# PointController.net
KiCad netlist of a schematic drawn in EAGLE
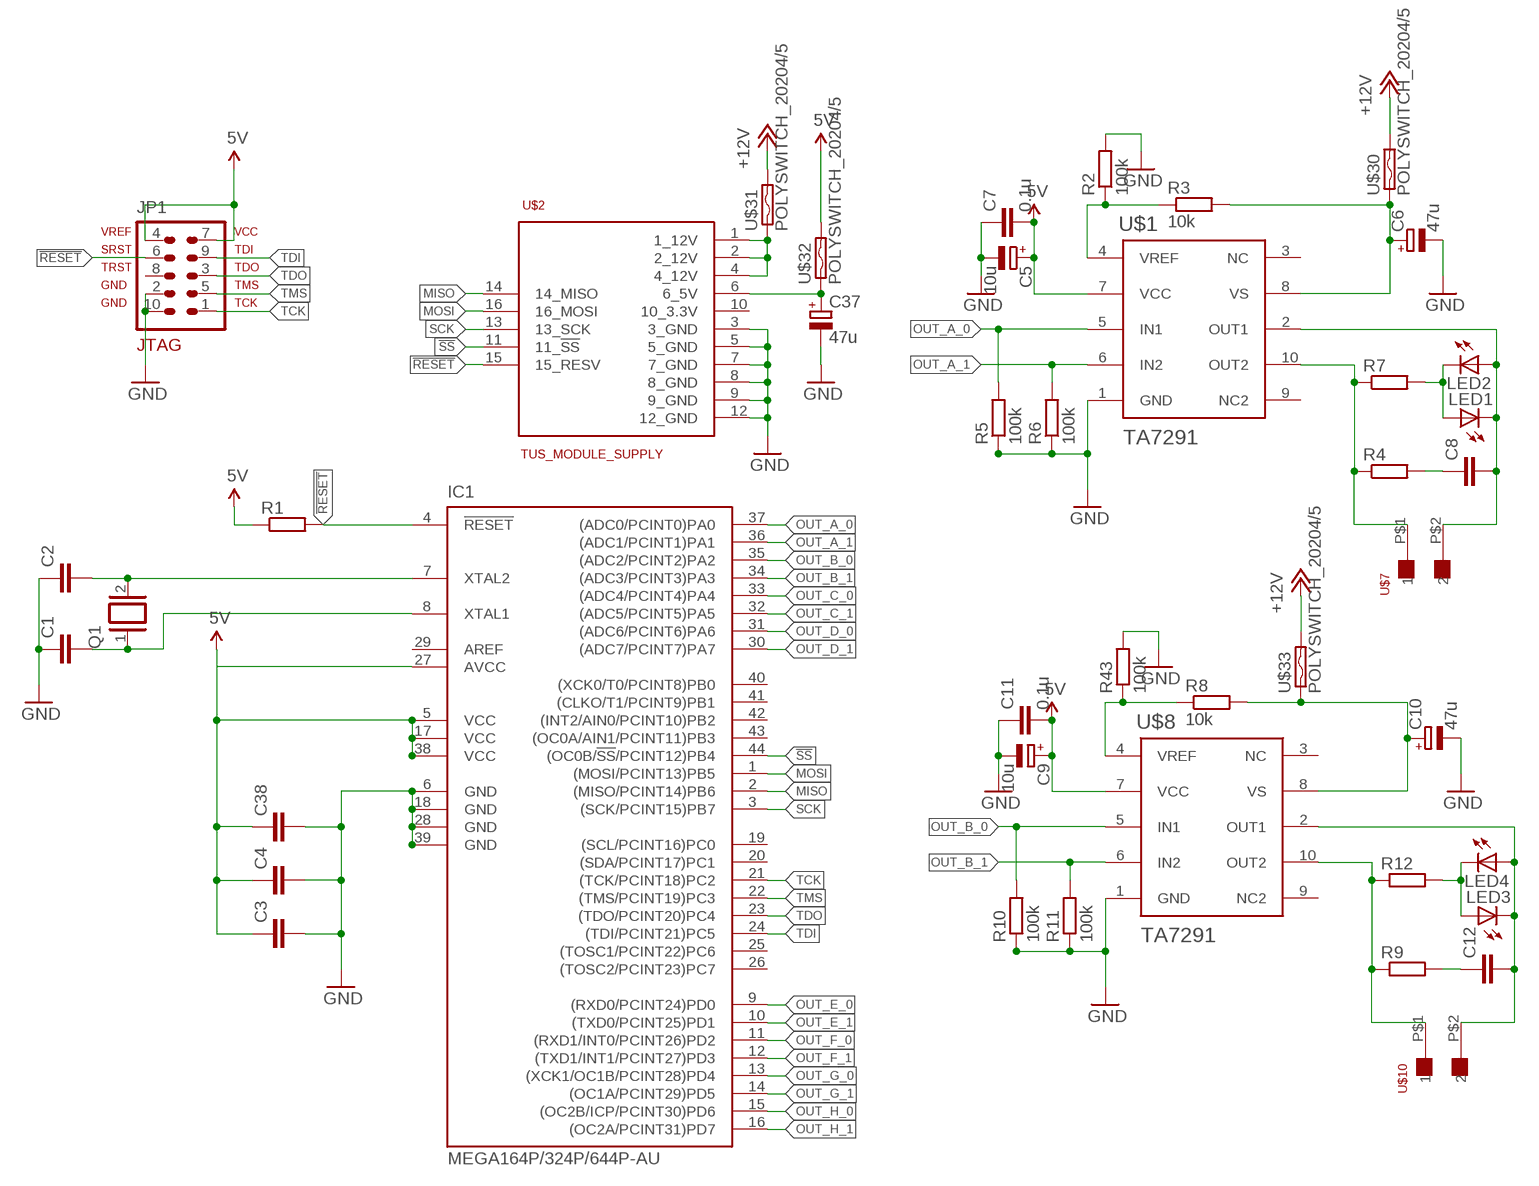
[diagram p0: schematic, sheet 1, part 1 of 2]
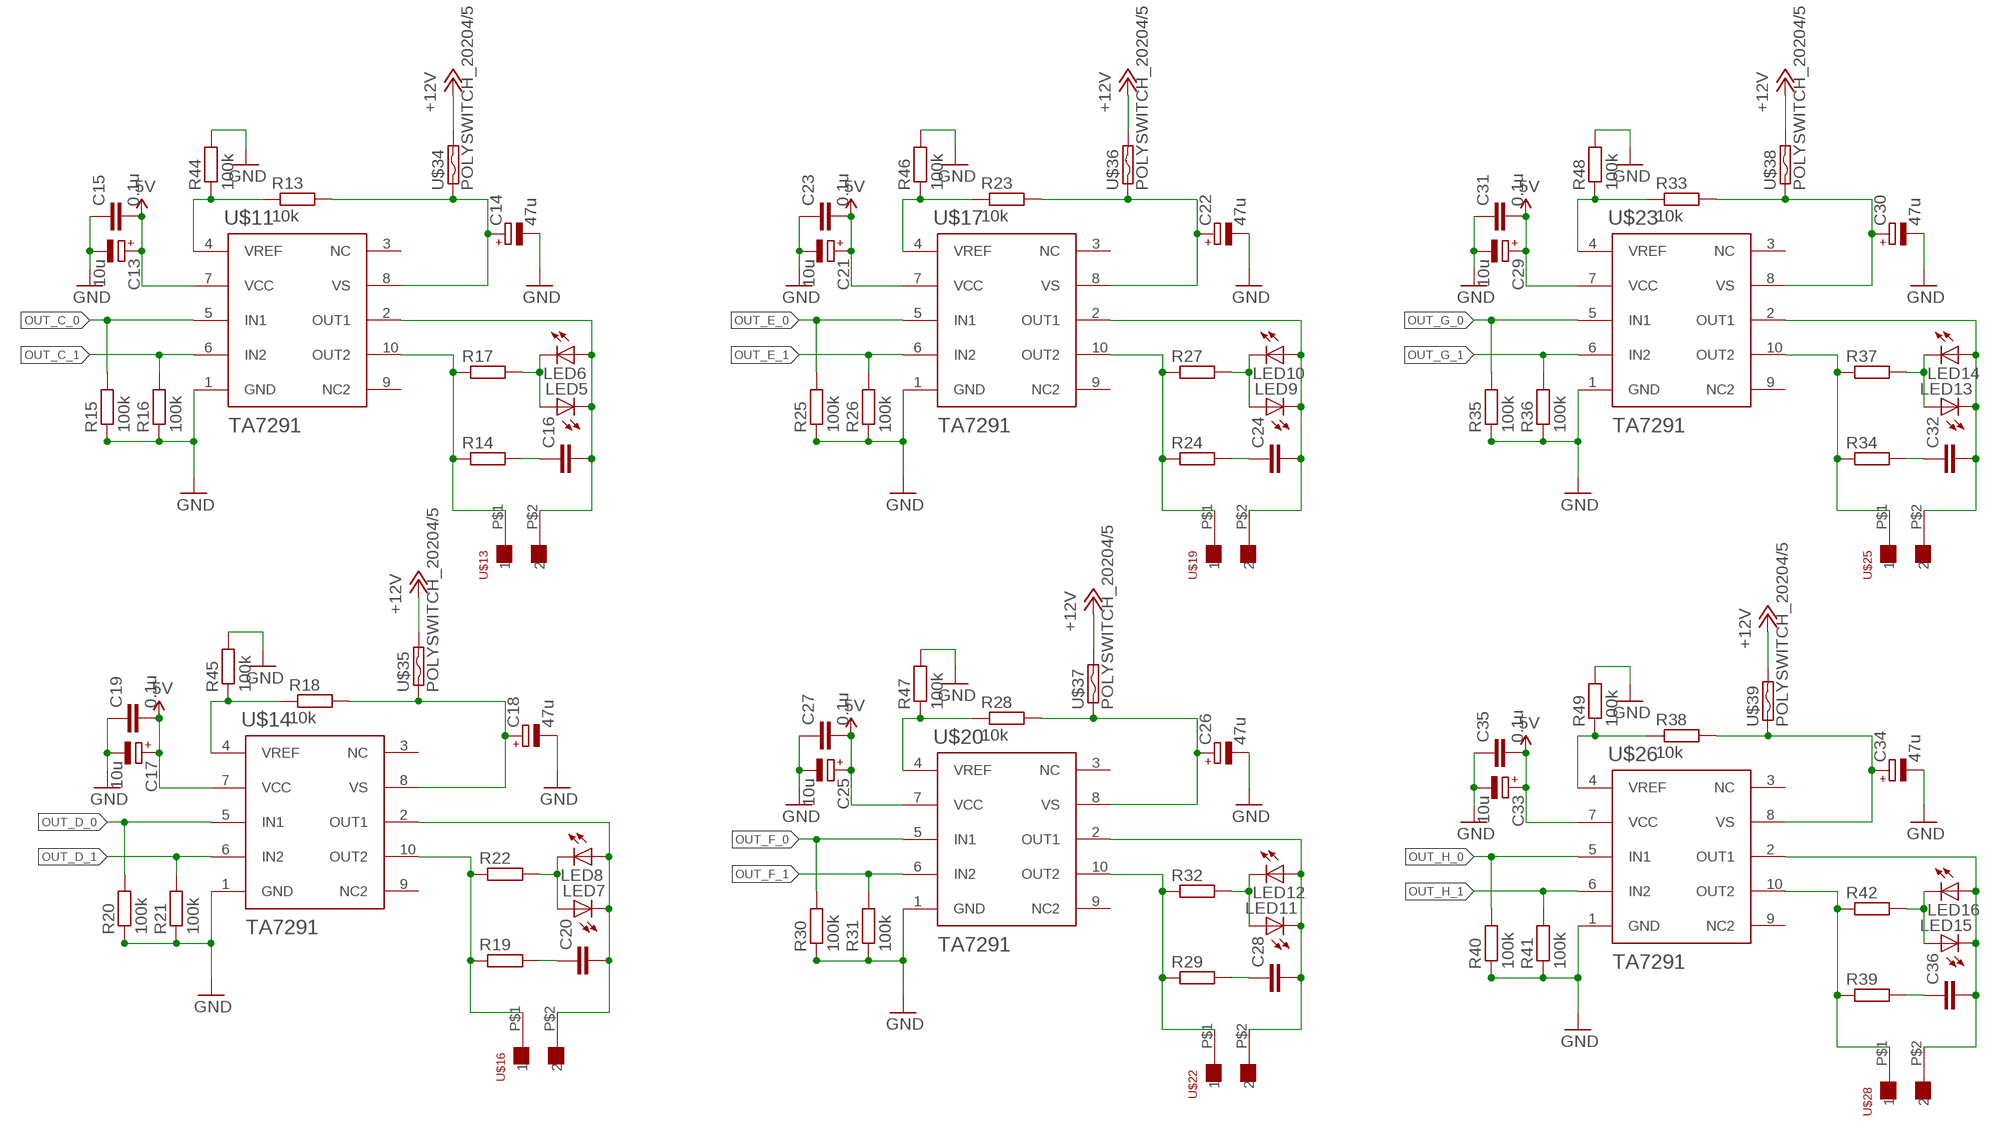
[diagram p1: schematic, sheet 1, part 2 of 2]

(export (version "E")
  (design (tool "Eeschema 10.0.6"))
  (components
    (comp (ref "C1")
      (value "C-EUC1608")
      (footprint "eagle-import:C1608")
      (libsource (lib "eagle-import") (part "C-EUC1608"))
    )
    (comp (ref "C2")
      (value "C-EUC1608")
      (footprint "eagle-import:C1608")
      (libsource (lib "eagle-import") (part "C-EUC1608"))
    )
    (comp (ref "C3")
      (value "C-EUC1608")
      (footprint "eagle-import:C1608")
      (libsource (lib "eagle-import") (part "C-EUC1608"))
    )
    (comp (ref "C4")
      (value "C-EUC1608")
      (footprint "eagle-import:C1608")
      (libsource (lib "eagle-import") (part "C-EUC1608"))
    )
    (comp (ref "C5")
      (value "10u")
      (footprint "eagle-import:E1,8-4")
      (libsource (lib "eagle-import") (part "CPOL-EUE1.8-4"))
    )
    (comp (ref "C6")
      (value "47u")
      (footprint "eagle-import:E1,8-4")
      (libsource (lib "eagle-import") (part "CPOL-EUE1.8-4"))
    )
    (comp (ref "C7")
      (value "0.1u")
      (footprint "eagle-import:C1608")
      (libsource (lib "eagle-import") (part "C-EUC1608"))
    )
    (comp (ref "C8")
      (value "C5/3")
      (footprint "eagle-import:C5B3")
      (libsource (lib "eagle-import") (part "C5/3"))
    )
    (comp (ref "C9")
      (value "10u")
      (footprint "eagle-import:E1,8-4")
      (libsource (lib "eagle-import") (part "CPOL-EUE1.8-4"))
    )
    (comp (ref "C10")
      (value "47u")
      (footprint "eagle-import:E1,8-4")
      (libsource (lib "eagle-import") (part "CPOL-EUE1.8-4"))
    )
    (comp (ref "C11")
      (value "0.1u")
      (footprint "eagle-import:C1608")
      (libsource (lib "eagle-import") (part "C-EUC1608"))
    )
    (comp (ref "C12")
      (value "C5/3")
      (footprint "eagle-import:C5B3")
      (libsource (lib "eagle-import") (part "C5/3"))
    )
    (comp (ref "C13")
      (value "10u")
      (footprint "eagle-import:E1,8-4")
      (libsource (lib "eagle-import") (part "CPOL-EUE1.8-4"))
    )
    (comp (ref "C14")
      (value "47u")
      (footprint "eagle-import:E1,8-4")
      (libsource (lib "eagle-import") (part "CPOL-EUE1.8-4"))
    )
    (comp (ref "C15")
      (value "0.1u")
      (footprint "eagle-import:C1608")
      (libsource (lib "eagle-import") (part "C-EUC1608"))
    )
    (comp (ref "C16")
      (value "C5/3")
      (footprint "eagle-import:C5B3")
      (libsource (lib "eagle-import") (part "C5/3"))
    )
    (comp (ref "C17")
      (value "10u")
      (footprint "eagle-import:E1,8-4")
      (libsource (lib "eagle-import") (part "CPOL-EUE1.8-4"))
    )
    (comp (ref "C18")
      (value "47u")
      (footprint "eagle-import:E1,8-4")
      (libsource (lib "eagle-import") (part "CPOL-EUE1.8-4"))
    )
    (comp (ref "C19")
      (value "0.1u")
      (footprint "eagle-import:C1608")
      (libsource (lib "eagle-import") (part "C-EUC1608"))
    )
    (comp (ref "C20")
      (value "C5/3")
      (footprint "eagle-import:C5B3")
      (libsource (lib "eagle-import") (part "C5/3"))
    )
    (comp (ref "C21")
      (value "10u")
      (footprint "eagle-import:E1,8-4")
      (libsource (lib "eagle-import") (part "CPOL-EUE1.8-4"))
    )
    (comp (ref "C22")
      (value "47u")
      (footprint "eagle-import:E1,8-4")
      (libsource (lib "eagle-import") (part "CPOL-EUE1.8-4"))
    )
    (comp (ref "C23")
      (value "0.1u")
      (footprint "eagle-import:C1608")
      (libsource (lib "eagle-import") (part "C-EUC1608"))
    )
    (comp (ref "C24")
      (value "C5/3")
      (footprint "eagle-import:C5B3")
      (libsource (lib "eagle-import") (part "C5/3"))
    )
    (comp (ref "C25")
      (value "10u")
      (footprint "eagle-import:E1,8-4")
      (libsource (lib "eagle-import") (part "CPOL-EUE1.8-4"))
    )
    (comp (ref "C26")
      (value "47u")
      (footprint "eagle-import:E1,8-4")
      (libsource (lib "eagle-import") (part "CPOL-EUE1.8-4"))
    )
    (comp (ref "C27")
      (value "0.1u")
      (footprint "eagle-import:C1608")
      (libsource (lib "eagle-import") (part "C-EUC1608"))
    )
    (comp (ref "C28")
      (value "C5/3")
      (footprint "eagle-import:C5B3")
      (libsource (lib "eagle-import") (part "C5/3"))
    )
    (comp (ref "C29")
      (value "10u")
      (footprint "eagle-import:E1,8-4")
      (libsource (lib "eagle-import") (part "CPOL-EUE1.8-4"))
    )
    (comp (ref "C30")
      (value "47u")
      (footprint "eagle-import:E1,8-4")
      (libsource (lib "eagle-import") (part "CPOL-EUE1.8-4"))
    )
    (comp (ref "C31")
      (value "0.1u")
      (footprint "eagle-import:C1608")
      (libsource (lib "eagle-import") (part "C-EUC1608"))
    )
    (comp (ref "C32")
      (value "C5/3")
      (footprint "eagle-import:C5B3")
      (libsource (lib "eagle-import") (part "C5/3"))
    )
    (comp (ref "C33")
      (value "10u")
      (footprint "eagle-import:E1,8-4")
      (libsource (lib "eagle-import") (part "CPOL-EUE1.8-4"))
    )
    (comp (ref "C34")
      (value "47u")
      (footprint "eagle-import:E1,8-4")
      (libsource (lib "eagle-import") (part "CPOL-EUE1.8-4"))
    )
    (comp (ref "C35")
      (value "0.1u")
      (footprint "eagle-import:C1608")
      (libsource (lib "eagle-import") (part "C-EUC1608"))
    )
    (comp (ref "C36")
      (value "C5/3")
      (footprint "eagle-import:C5B3")
      (libsource (lib "eagle-import") (part "C5/3"))
    )
    (comp (ref "C37")
      (value "47u")
      (footprint "eagle-import:E1,8-4")
      (libsource (lib "eagle-import") (part "CPOL-EUE1.8-4"))
    )
    (comp (ref "C38")
      (value "C-EUC1608")
      (footprint "eagle-import:C1608")
      (libsource (lib "eagle-import") (part "C-EUC1608"))
    )
    (comp (ref "IC1")
      (value "MEGA164P/324P/644P-AU")
      (footprint "eagle-import:TQFP44")
      (libsource (lib "eagle-import") (part "MEGA164P/324P/644P-AU"))
    )
    (comp (ref "JP1")
      (value "AVR-JTAG-10")
      (footprint "eagle-import:AVR-JTAG-10")
      (libsource (lib "eagle-import") (part "AVR-JTAG-10"))
    )
    (comp (ref "LED1")
      (value "LED3MM")
      (footprint "eagle-import:LED3MM")
      (libsource (lib "eagle-import") (part "LED3MM"))
    )
    (comp (ref "LED2")
      (value "LED3MM")
      (footprint "eagle-import:LED3MM")
      (libsource (lib "eagle-import") (part "LED3MM"))
    )
    (comp (ref "LED3")
      (value "LED3MM")
      (footprint "eagle-import:LED3MM")
      (libsource (lib "eagle-import") (part "LED3MM"))
    )
    (comp (ref "LED4")
      (value "LED3MM")
      (footprint "eagle-import:LED3MM")
      (libsource (lib "eagle-import") (part "LED3MM"))
    )
    (comp (ref "LED5")
      (value "LED3MM")
      (footprint "eagle-import:LED3MM")
      (libsource (lib "eagle-import") (part "LED3MM"))
    )
    (comp (ref "LED6")
      (value "LED3MM")
      (footprint "eagle-import:LED3MM")
      (libsource (lib "eagle-import") (part "LED3MM"))
    )
    (comp (ref "LED7")
      (value "LED3MM")
      (footprint "eagle-import:LED3MM")
      (libsource (lib "eagle-import") (part "LED3MM"))
    )
    (comp (ref "LED8")
      (value "LED3MM")
      (footprint "eagle-import:LED3MM")
      (libsource (lib "eagle-import") (part "LED3MM"))
    )
    (comp (ref "LED9")
      (value "LED3MM")
      (footprint "eagle-import:LED3MM")
      (libsource (lib "eagle-import") (part "LED3MM"))
    )
    (comp (ref "LED10")
      (value "LED3MM")
      (footprint "eagle-import:LED3MM")
      (libsource (lib "eagle-import") (part "LED3MM"))
    )
    (comp (ref "LED11")
      (value "LED3MM")
      (footprint "eagle-import:LED3MM")
      (libsource (lib "eagle-import") (part "LED3MM"))
    )
    (comp (ref "LED12")
      (value "LED3MM")
      (footprint "eagle-import:LED3MM")
      (libsource (lib "eagle-import") (part "LED3MM"))
    )
    (comp (ref "LED13")
      (value "LED3MM")
      (footprint "eagle-import:LED3MM")
      (libsource (lib "eagle-import") (part "LED3MM"))
    )
    (comp (ref "LED14")
      (value "LED3MM")
      (footprint "eagle-import:LED3MM")
      (libsource (lib "eagle-import") (part "LED3MM"))
    )
    (comp (ref "LED15")
      (value "LED3MM")
      (footprint "eagle-import:LED3MM")
      (libsource (lib "eagle-import") (part "LED3MM"))
    )
    (comp (ref "LED16")
      (value "LED3MM")
      (footprint "eagle-import:LED3MM")
      (libsource (lib "eagle-import") (part "LED3MM"))
    )
    (comp (ref "Q1")
      (value "XTAL/S")
      (footprint "eagle-import:QS")
      (libsource (lib "eagle-import") (part "XTAL/S"))
    )
    (comp (ref "R1")
      (value "R-EU_R0603")
      (footprint "eagle-import:R0603")
      (libsource (lib "eagle-import") (part "R-EU_R0603"))
    )
    (comp (ref "R2")
      (value "100k")
      (footprint "eagle-import:R0603")
      (libsource (lib "eagle-import") (part "R-EU_R0603"))
    )
    (comp (ref "R3")
      (value "10k")
      (footprint "eagle-import:R0603")
      (libsource (lib "eagle-import") (part "R-EU_R0603"))
    )
    (comp (ref "R4")
      (value "R-EU_0204/7")
      (footprint "eagle-import:0204_7")
      (libsource (lib "eagle-import") (part "resistor_R-EU_0204/7"))
    )
    (comp (ref "R5")
      (value "100k")
      (footprint "eagle-import:R0603")
      (libsource (lib "eagle-import") (part "R-EU_R0603"))
    )
    (comp (ref "R6")
      (value "100k")
      (footprint "eagle-import:R0603")
      (libsource (lib "eagle-import") (part "R-EU_R0603"))
    )
    (comp (ref "R7")
      (value "R-EU_0204/7")
      (footprint "eagle-import:0204_7")
      (libsource (lib "eagle-import") (part "resistor_R-EU_0204/7"))
    )
    (comp (ref "R8")
      (value "10k")
      (footprint "eagle-import:R0603")
      (libsource (lib "eagle-import") (part "R-EU_R0603"))
    )
    (comp (ref "R9")
      (value "R-EU_0204/7")
      (footprint "eagle-import:0204_7")
      (libsource (lib "eagle-import") (part "resistor_R-EU_0204/7"))
    )
    (comp (ref "R10")
      (value "100k")
      (footprint "eagle-import:R0603")
      (libsource (lib "eagle-import") (part "R-EU_R0603"))
    )
    (comp (ref "R11")
      (value "100k")
      (footprint "eagle-import:R0603")
      (libsource (lib "eagle-import") (part "R-EU_R0603"))
    )
    (comp (ref "R12")
      (value "R-EU_0204/7")
      (footprint "eagle-import:0204_7")
      (libsource (lib "eagle-import") (part "resistor_R-EU_0204/7"))
    )
    (comp (ref "R13")
      (value "10k")
      (footprint "eagle-import:R0603")
      (libsource (lib "eagle-import") (part "R-EU_R0603"))
    )
    (comp (ref "R14")
      (value "R-EU_0204/7")
      (footprint "eagle-import:0204_7")
      (libsource (lib "eagle-import") (part "resistor_R-EU_0204/7"))
    )
    (comp (ref "R15")
      (value "100k")
      (footprint "eagle-import:R0603")
      (libsource (lib "eagle-import") (part "R-EU_R0603"))
    )
    (comp (ref "R16")
      (value "100k")
      (footprint "eagle-import:R0603")
      (libsource (lib "eagle-import") (part "R-EU_R0603"))
    )
    (comp (ref "R17")
      (value "R-EU_0204/7")
      (footprint "eagle-import:0204_7")
      (libsource (lib "eagle-import") (part "resistor_R-EU_0204/7"))
    )
    (comp (ref "R18")
      (value "10k")
      (footprint "eagle-import:R0603")
      (libsource (lib "eagle-import") (part "R-EU_R0603"))
    )
    (comp (ref "R19")
      (value "R-EU_0204/7")
      (footprint "eagle-import:0204_7")
      (libsource (lib "eagle-import") (part "resistor_R-EU_0204/7"))
    )
    (comp (ref "R20")
      (value "100k")
      (footprint "eagle-import:R0603")
      (libsource (lib "eagle-import") (part "R-EU_R0603"))
    )
    (comp (ref "R21")
      (value "100k")
      (footprint "eagle-import:R0603")
      (libsource (lib "eagle-import") (part "R-EU_R0603"))
    )
    (comp (ref "R22")
      (value "R-EU_0204/7")
      (footprint "eagle-import:0204_7")
      (libsource (lib "eagle-import") (part "resistor_R-EU_0204/7"))
    )
    (comp (ref "R23")
      (value "10k")
      (footprint "eagle-import:R0603")
      (libsource (lib "eagle-import") (part "R-EU_R0603"))
    )
    (comp (ref "R24")
      (value "R-EU_0204/7")
      (footprint "eagle-import:0204_7")
      (libsource (lib "eagle-import") (part "resistor_R-EU_0204/7"))
    )
    (comp (ref "R25")
      (value "100k")
      (footprint "eagle-import:R0603")
      (libsource (lib "eagle-import") (part "R-EU_R0603"))
    )
    (comp (ref "R26")
      (value "100k")
      (footprint "eagle-import:R0603")
      (libsource (lib "eagle-import") (part "R-EU_R0603"))
    )
    (comp (ref "R27")
      (value "R-EU_0204/7")
      (footprint "eagle-import:0204_7")
      (libsource (lib "eagle-import") (part "resistor_R-EU_0204/7"))
    )
    (comp (ref "R28")
      (value "10k")
      (footprint "eagle-import:R0603")
      (libsource (lib "eagle-import") (part "R-EU_R0603"))
    )
    (comp (ref "R29")
      (value "R-EU_0204/7")
      (footprint "eagle-import:0204_7")
      (libsource (lib "eagle-import") (part "resistor_R-EU_0204/7"))
    )
    (comp (ref "R30")
      (value "100k")
      (footprint "eagle-import:R0603")
      (libsource (lib "eagle-import") (part "R-EU_R0603"))
    )
    (comp (ref "R31")
      (value "100k")
      (footprint "eagle-import:R0603")
      (libsource (lib "eagle-import") (part "R-EU_R0603"))
    )
    (comp (ref "R32")
      (value "R-EU_0204/7")
      (footprint "eagle-import:0204_7")
      (libsource (lib "eagle-import") (part "resistor_R-EU_0204/7"))
    )
    (comp (ref "R33")
      (value "10k")
      (footprint "eagle-import:R0603")
      (libsource (lib "eagle-import") (part "R-EU_R0603"))
    )
    (comp (ref "R34")
      (value "R-EU_0204/7")
      (footprint "eagle-import:0204_7")
      (libsource (lib "eagle-import") (part "resistor_R-EU_0204/7"))
    )
    (comp (ref "R35")
      (value "100k")
      (footprint "eagle-import:R0603")
      (libsource (lib "eagle-import") (part "R-EU_R0603"))
    )
    (comp (ref "R36")
      (value "100k")
      (footprint "eagle-import:R0603")
      (libsource (lib "eagle-import") (part "R-EU_R0603"))
    )
    (comp (ref "R37")
      (value "R-EU_0204/7")
      (footprint "eagle-import:0204_7")
      (libsource (lib "eagle-import") (part "resistor_R-EU_0204/7"))
    )
    (comp (ref "R38")
      (value "10k")
      (footprint "eagle-import:R0603")
      (libsource (lib "eagle-import") (part "R-EU_R0603"))
    )
    (comp (ref "R39")
      (value "R-EU_0204/7")
      (footprint "eagle-import:0204_7")
      (libsource (lib "eagle-import") (part "resistor_R-EU_0204/7"))
    )
    (comp (ref "R40")
      (value "100k")
      (footprint "eagle-import:R0603")
      (libsource (lib "eagle-import") (part "R-EU_R0603"))
    )
    (comp (ref "R41")
      (value "100k")
      (footprint "eagle-import:R0603")
      (libsource (lib "eagle-import") (part "R-EU_R0603"))
    )
    (comp (ref "R42")
      (value "R-EU_0204/7")
      (footprint "eagle-import:0204_7")
      (libsource (lib "eagle-import") (part "resistor_R-EU_0204/7"))
    )
    (comp (ref "R43")
      (value "100k")
      (footprint "eagle-import:R0603")
      (libsource (lib "eagle-import") (part "R-EU_R0603"))
    )
    (comp (ref "R44")
      (value "100k")
      (footprint "eagle-import:R0603")
      (libsource (lib "eagle-import") (part "R-EU_R0603"))
    )
    (comp (ref "R45")
      (value "100k")
      (footprint "eagle-import:R0603")
      (libsource (lib "eagle-import") (part "R-EU_R0603"))
    )
    (comp (ref "R46")
      (value "100k")
      (footprint "eagle-import:R0603")
      (libsource (lib "eagle-import") (part "R-EU_R0603"))
    )
    (comp (ref "R47")
      (value "100k")
      (footprint "eagle-import:R0603")
      (libsource (lib "eagle-import") (part "R-EU_R0603"))
    )
    (comp (ref "R48")
      (value "100k")
      (footprint "eagle-import:R0603")
      (libsource (lib "eagle-import") (part "R-EU_R0603"))
    )
    (comp (ref "R49")
      (value "100k")
      (footprint "eagle-import:R0603")
      (libsource (lib "eagle-import") (part "R-EU_R0603"))
    )
    (comp (ref "U$1")
      (value "TA7291")
      (footprint "eagle-import:HSIP10")
      (libsource (lib "eagle-import") (part "TA7291"))
    )
    (comp (ref "U$2")
      (value "TUS_MODULE_SUPPLY")
      (footprint "eagle-import:2X08")
      (libsource (lib "eagle-import") (part "TUS_MODULE_SUPPLY"))
    )
    (comp (ref "U$7")
      (value "XH-2")
      (footprint "eagle-import:XH-2")
      (libsource (lib "eagle-import") (part "XH-2"))
    )
    (comp (ref "U$8")
      (value "TA7291")
      (footprint "eagle-import:HSIP10")
      (libsource (lib "eagle-import") (part "TA7291"))
    )
    (comp (ref "U$10")
      (value "XH-2")
      (footprint "eagle-import:XH-2")
      (libsource (lib "eagle-import") (part "XH-2"))
    )
    (comp (ref "U$11")
      (value "TA7291")
      (footprint "eagle-import:HSIP10")
      (libsource (lib "eagle-import") (part "TA7291"))
    )
    (comp (ref "U$13")
      (value "XH-2")
      (footprint "eagle-import:XH-2")
      (libsource (lib "eagle-import") (part "XH-2"))
    )
    (comp (ref "U$14")
      (value "TA7291")
      (footprint "eagle-import:HSIP10")
      (libsource (lib "eagle-import") (part "TA7291"))
    )
    (comp (ref "U$16")
      (value "XH-2")
      (footprint "eagle-import:XH-2")
      (libsource (lib "eagle-import") (part "XH-2"))
    )
    (comp (ref "U$17")
      (value "TA7291")
      (footprint "eagle-import:HSIP10")
      (libsource (lib "eagle-import") (part "TA7291"))
    )
    (comp (ref "U$19")
      (value "XH-2")
      (footprint "eagle-import:XH-2")
      (libsource (lib "eagle-import") (part "XH-2"))
    )
    (comp (ref "U$20")
      (value "TA7291")
      (footprint "eagle-import:HSIP10")
      (libsource (lib "eagle-import") (part "TA7291"))
    )
    (comp (ref "U$22")
      (value "XH-2")
      (footprint "eagle-import:XH-2")
      (libsource (lib "eagle-import") (part "XH-2"))
    )
    (comp (ref "U$23")
      (value "TA7291")
      (footprint "eagle-import:HSIP10")
      (libsource (lib "eagle-import") (part "TA7291"))
    )
    (comp (ref "U$25")
      (value "XH-2")
      (footprint "eagle-import:XH-2")
      (libsource (lib "eagle-import") (part "XH-2"))
    )
    (comp (ref "U$26")
      (value "TA7291")
      (footprint "eagle-import:HSIP10")
      (libsource (lib "eagle-import") (part "TA7291"))
    )
    (comp (ref "U$28")
      (value "XH-2")
      (footprint "eagle-import:XH-2")
      (libsource (lib "eagle-import") (part "XH-2"))
    )
    (comp (ref "U$30")
      (value "POLYSWITCH_20204/5")
      (footprint "eagle-import:0204_5")
      (libsource (lib "eagle-import") (part "POLYSWITCH_20204/5"))
    )
    (comp (ref "U$31")
      (value "POLYSWITCH_20204/5")
      (footprint "eagle-import:0204_5")
      (libsource (lib "eagle-import") (part "POLYSWITCH_20204/5"))
    )
    (comp (ref "U$32")
      (value "POLYSWITCH_20204/5")
      (footprint "eagle-import:0204_5")
      (libsource (lib "eagle-import") (part "POLYSWITCH_20204/5"))
    )
    (comp (ref "U$33")
      (value "POLYSWITCH_20204/5")
      (footprint "eagle-import:0204_5")
      (libsource (lib "eagle-import") (part "POLYSWITCH_20204/5"))
    )
    (comp (ref "U$34")
      (value "POLYSWITCH_20204/5")
      (footprint "eagle-import:0204_5")
      (libsource (lib "eagle-import") (part "POLYSWITCH_20204/5"))
    )
    (comp (ref "U$35")
      (value "POLYSWITCH_20204/5")
      (footprint "eagle-import:0204_5")
      (libsource (lib "eagle-import") (part "POLYSWITCH_20204/5"))
    )
    (comp (ref "U$36")
      (value "POLYSWITCH_20204/5")
      (footprint "eagle-import:0204_5")
      (libsource (lib "eagle-import") (part "POLYSWITCH_20204/5"))
    )
    (comp (ref "U$37")
      (value "POLYSWITCH_20204/5")
      (footprint "eagle-import:0204_5")
      (libsource (lib "eagle-import") (part "POLYSWITCH_20204/5"))
    )
    (comp (ref "U$38")
      (value "POLYSWITCH_20204/5")
      (footprint "eagle-import:0204_5")
      (libsource (lib "eagle-import") (part "POLYSWITCH_20204/5"))
    )
    (comp (ref "U$39")
      (value "POLYSWITCH_20204/5")
      (footprint "eagle-import:0204_5")
      (libsource (lib "eagle-import") (part "POLYSWITCH_20204/5"))
    )
  )
  (nets
    (net (code "1") (name "+12V") (class "Default")
      (node (ref "U$30") (pin "2") (pinfunction "2_2") (pintype "passive"))
      (node (ref "U$31") (pin "2") (pinfunction "2_2") (pintype "passive"))
      (node (ref "U$33") (pin "2") (pinfunction "2_2") (pintype "passive"))
      (node (ref "U$34") (pin "2") (pinfunction "2_2") (pintype "passive"))
      (node (ref "U$35") (pin "2") (pinfunction "2_2") (pintype "passive"))
      (node (ref "U$36") (pin "2") (pinfunction "2_2") (pintype "passive"))
      (node (ref "U$37") (pin "2") (pinfunction "2_2") (pintype "passive"))
      (node (ref "U$38") (pin "2") (pinfunction "2_2") (pintype "passive"))
      (node (ref "U$39") (pin "2") (pinfunction "2_2") (pintype "passive"))
    )
    (net (code "2") (name "/AREF") (class "Default")
      (node (ref "IC1") (pin "29") (pinfunction "AREF_29") (pintype "power_in"))
    )
    (net (code "3") (name "/~{RESET}") (class "Default")
      (node (ref "IC1") (pin "4") (pinfunction "~{RESET}_4") (pintype "input"))
      (node (ref "JP1") (pin "6") (pinfunction "6_6") (pintype "passive"))
      (node (ref "R1") (pin "2") (pinfunction "2_2") (pintype "passive"))
      (node (ref "U$2") (pin "15") (pinfunction "15_RESV_15") (pintype "bidirectional"))
    )
    (net (code "4") (name "/~{SS}") (class "Default")
      (node (ref "IC1") (pin "44") (pinfunction "(OC0B/~{SS}/PCINT12)PB4_44") (pintype "bidirectional"))
      (node (ref "U$2") (pin "11") (pinfunction "11_~{SS}_11") (pintype "bidirectional"))
    )
    (net (code "5") (name "5V") (class "Default")
      (node (ref "C11") (pin "2") (pinfunction "2_2") (pintype "passive"))
      (node (ref "C13") (pin "+") (pinfunction "+_+") (pintype "passive"))
      (node (ref "C15") (pin "2") (pinfunction "2_2") (pintype "passive"))
      (node (ref "C17") (pin "+") (pinfunction "+_+") (pintype "passive"))
      (node (ref "C19") (pin "2") (pinfunction "2_2") (pintype "passive"))
      (node (ref "C21") (pin "+") (pinfunction "+_+") (pintype "passive"))
      (node (ref "C23") (pin "2") (pinfunction "2_2") (pintype "passive"))
      (node (ref "C25") (pin "+") (pinfunction "+_+") (pintype "passive"))
      (node (ref "C27") (pin "2") (pinfunction "2_2") (pintype "passive"))
      (node (ref "C29") (pin "+") (pinfunction "+_+") (pintype "passive"))
      (node (ref "C3") (pin "1") (pinfunction "1_1") (pintype "passive"))
      (node (ref "C31") (pin "2") (pinfunction "2_2") (pintype "passive"))
      (node (ref "C33") (pin "+") (pinfunction "+_+") (pintype "passive"))
      (node (ref "C35") (pin "2") (pinfunction "2_2") (pintype "passive"))
      (node (ref "C38") (pin "1") (pinfunction "1_1") (pintype "passive"))
      (node (ref "C4") (pin "1") (pinfunction "1_1") (pintype "passive"))
      (node (ref "C5") (pin "+") (pinfunction "+_+") (pintype "passive"))
      (node (ref "C7") (pin "2") (pinfunction "2_2") (pintype "passive"))
      (node (ref "C9") (pin "+") (pinfunction "+_+") (pintype "passive"))
      (node (ref "IC1") (pin "17") (pinfunction "VCC_17") (pintype "power_in"))
      (node (ref "IC1") (pin "27") (pinfunction "AVCC_27") (pintype "power_in"))
      (node (ref "IC1") (pin "38") (pinfunction "VCC_38") (pintype "power_in"))
      (node (ref "IC1") (pin "5") (pinfunction "VCC_5") (pintype "power_in"))
      (node (ref "JP1") (pin "4") (pinfunction "4_4") (pintype "passive"))
      (node (ref "JP1") (pin "7") (pinfunction "7_7") (pintype "passive"))
      (node (ref "R1") (pin "1") (pinfunction "1_1") (pintype "passive"))
      (node (ref "U$1") (pin "7") (pinfunction "VCC_7") (pintype "bidirectional"))
      (node (ref "U$11") (pin "7") (pinfunction "VCC_7") (pintype "bidirectional"))
      (node (ref "U$14") (pin "7") (pinfunction "VCC_7") (pintype "bidirectional"))
      (node (ref "U$17") (pin "7") (pinfunction "VCC_7") (pintype "bidirectional"))
      (node (ref "U$20") (pin "7") (pinfunction "VCC_7") (pintype "bidirectional"))
      (node (ref "U$23") (pin "7") (pinfunction "VCC_7") (pintype "bidirectional"))
      (node (ref "U$26") (pin "7") (pinfunction "VCC_7") (pintype "bidirectional"))
      (node (ref "U$32") (pin "2") (pinfunction "2_2") (pintype "passive"))
      (node (ref "U$8") (pin "7") (pinfunction "VCC_7") (pintype "bidirectional"))
    )
    (net (code "6") (name "GND") (class "Default")
      (node (ref "C1") (pin "1") (pinfunction "1_1") (pintype "passive"))
      (node (ref "C10") (pin "-") (pinfunction "-_-") (pintype "passive"))
      (node (ref "C11") (pin "1") (pinfunction "1_1") (pintype "passive"))
      (node (ref "C13") (pin "-") (pinfunction "-_-") (pintype "passive"))
      (node (ref "C14") (pin "-") (pinfunction "-_-") (pintype "passive"))
      (node (ref "C15") (pin "1") (pinfunction "1_1") (pintype "passive"))
      (node (ref "C17") (pin "-") (pinfunction "-_-") (pintype "passive"))
      (node (ref "C18") (pin "-") (pinfunction "-_-") (pintype "passive"))
      (node (ref "C19") (pin "1") (pinfunction "1_1") (pintype "passive"))
      (node (ref "C2") (pin "1") (pinfunction "1_1") (pintype "passive"))
      (node (ref "C21") (pin "-") (pinfunction "-_-") (pintype "passive"))
      (node (ref "C22") (pin "-") (pinfunction "-_-") (pintype "passive"))
      (node (ref "C23") (pin "1") (pinfunction "1_1") (pintype "passive"))
      (node (ref "C25") (pin "-") (pinfunction "-_-") (pintype "passive"))
      (node (ref "C26") (pin "-") (pinfunction "-_-") (pintype "passive"))
      (node (ref "C27") (pin "1") (pinfunction "1_1") (pintype "passive"))
      (node (ref "C29") (pin "-") (pinfunction "-_-") (pintype "passive"))
      (node (ref "C3") (pin "2") (pinfunction "2_2") (pintype "passive"))
      (node (ref "C30") (pin "-") (pinfunction "-_-") (pintype "passive"))
      (node (ref "C31") (pin "1") (pinfunction "1_1") (pintype "passive"))
      (node (ref "C33") (pin "-") (pinfunction "-_-") (pintype "passive"))
      (node (ref "C34") (pin "-") (pinfunction "-_-") (pintype "passive"))
      (node (ref "C35") (pin "1") (pinfunction "1_1") (pintype "passive"))
      (node (ref "C37") (pin "-") (pinfunction "-_-") (pintype "passive"))
      (node (ref "C38") (pin "2") (pinfunction "2_2") (pintype "passive"))
      (node (ref "C4") (pin "2") (pinfunction "2_2") (pintype "passive"))
      (node (ref "C5") (pin "-") (pinfunction "-_-") (pintype "passive"))
      (node (ref "C6") (pin "-") (pinfunction "-_-") (pintype "passive"))
      (node (ref "C7") (pin "1") (pinfunction "1_1") (pintype "passive"))
      (node (ref "C9") (pin "-") (pinfunction "-_-") (pintype "passive"))
      (node (ref "IC1") (pin "18") (pinfunction "GND_18") (pintype "power_in"))
      (node (ref "IC1") (pin "28") (pinfunction "GND_28") (pintype "power_in"))
      (node (ref "IC1") (pin "39") (pinfunction "GND_39") (pintype "power_in"))
      (node (ref "IC1") (pin "6") (pinfunction "GND_6") (pintype "power_in"))
      (node (ref "JP1") (pin "10") (pinfunction "10_10") (pintype "passive"))
      (node (ref "JP1") (pin "2") (pinfunction "2_2") (pintype "passive"))
      (node (ref "R10") (pin "1") (pinfunction "1_1") (pintype "passive"))
      (node (ref "R11") (pin "1") (pinfunction "1_1") (pintype "passive"))
      (node (ref "R15") (pin "1") (pinfunction "1_1") (pintype "passive"))
      (node (ref "R16") (pin "1") (pinfunction "1_1") (pintype "passive"))
      (node (ref "R2") (pin "2") (pinfunction "2_2") (pintype "passive"))
      (node (ref "R20") (pin "1") (pinfunction "1_1") (pintype "passive"))
      (node (ref "R21") (pin "1") (pinfunction "1_1") (pintype "passive"))
      (node (ref "R25") (pin "1") (pinfunction "1_1") (pintype "passive"))
      (node (ref "R26") (pin "1") (pinfunction "1_1") (pintype "passive"))
      (node (ref "R30") (pin "1") (pinfunction "1_1") (pintype "passive"))
      (node (ref "R31") (pin "1") (pinfunction "1_1") (pintype "passive"))
      (node (ref "R35") (pin "1") (pinfunction "1_1") (pintype "passive"))
      (node (ref "R36") (pin "1") (pinfunction "1_1") (pintype "passive"))
      (node (ref "R40") (pin "1") (pinfunction "1_1") (pintype "passive"))
      (node (ref "R41") (pin "1") (pinfunction "1_1") (pintype "passive"))
      (node (ref "R43") (pin "2") (pinfunction "2_2") (pintype "passive"))
      (node (ref "R44") (pin "2") (pinfunction "2_2") (pintype "passive"))
      (node (ref "R45") (pin "2") (pinfunction "2_2") (pintype "passive"))
      (node (ref "R46") (pin "2") (pinfunction "2_2") (pintype "passive"))
      (node (ref "R47") (pin "2") (pinfunction "2_2") (pintype "passive"))
      (node (ref "R48") (pin "2") (pinfunction "2_2") (pintype "passive"))
      (node (ref "R49") (pin "2") (pinfunction "2_2") (pintype "passive"))
      (node (ref "R5") (pin "1") (pinfunction "1_1") (pintype "passive"))
      (node (ref "R6") (pin "1") (pinfunction "1_1") (pintype "passive"))
      (node (ref "U$1") (pin "1") (pinfunction "GND_1") (pintype "bidirectional"))
      (node (ref "U$11") (pin "1") (pinfunction "GND_1") (pintype "bidirectional"))
      (node (ref "U$14") (pin "1") (pinfunction "GND_1") (pintype "bidirectional"))
      (node (ref "U$17") (pin "1") (pinfunction "GND_1") (pintype "bidirectional"))
      (node (ref "U$2") (pin "12") (pinfunction "12_GND_12") (pintype "bidirectional"))
      (node (ref "U$2") (pin "3") (pinfunction "3_GND_3") (pintype "bidirectional"))
      (node (ref "U$2") (pin "5") (pinfunction "5_GND_5") (pintype "bidirectional"))
      (node (ref "U$2") (pin "7") (pinfunction "7_GND_7") (pintype "bidirectional"))
      (node (ref "U$2") (pin "8") (pinfunction "8_GND_8") (pintype "bidirectional"))
      (node (ref "U$2") (pin "9") (pinfunction "9_GND_9") (pintype "bidirectional"))
      (node (ref "U$20") (pin "1") (pinfunction "GND_1") (pintype "bidirectional"))
      (node (ref "U$23") (pin "1") (pinfunction "GND_1") (pintype "bidirectional"))
      (node (ref "U$26") (pin "1") (pinfunction "GND_1") (pintype "bidirectional"))
      (node (ref "U$8") (pin "1") (pinfunction "GND_1") (pintype "bidirectional"))
    )
    (net (code "7") (name "MISO") (class "Default")
      (node (ref "IC1") (pin "2") (pinfunction "(MISO/PCINT14)PB6_2") (pintype "bidirectional"))
      (node (ref "U$2") (pin "14") (pinfunction "14_MISO_14") (pintype "bidirectional"))
    )
    (net (code "8") (name "MOSI") (class "Default")
      (node (ref "IC1") (pin "1") (pinfunction "(MOSI/PCINT13)PB5_1") (pintype "bidirectional"))
      (node (ref "U$2") (pin "16") (pinfunction "16_MOSI_16") (pintype "bidirectional"))
    )
    (net (code "9") (name "Net-(C8-Pad1)") (class "Default")
      (node (ref "C8") (pin "1") (pinfunction "1_1") (pintype "passive"))
      (node (ref "R4") (pin "2") (pinfunction "2_2") (pintype "passive"))
    )
    (net (code "10") (name "Net-(C12-Pad1)") (class "Default")
      (node (ref "C12") (pin "1") (pinfunction "1_1") (pintype "passive"))
      (node (ref "R9") (pin "2") (pinfunction "2_2") (pintype "passive"))
    )
    (net (code "11") (name "Net-(C16-Pad1)") (class "Default")
      (node (ref "C16") (pin "1") (pinfunction "1_1") (pintype "passive"))
      (node (ref "R14") (pin "2") (pinfunction "2_2") (pintype "passive"))
    )
    (net (code "12") (name "Net-(C20-Pad1)") (class "Default")
      (node (ref "C20") (pin "1") (pinfunction "1_1") (pintype "passive"))
      (node (ref "R19") (pin "2") (pinfunction "2_2") (pintype "passive"))
    )
    (net (code "13") (name "Net-(C24-Pad1)") (class "Default")
      (node (ref "C24") (pin "1") (pinfunction "1_1") (pintype "passive"))
      (node (ref "R24") (pin "2") (pinfunction "2_2") (pintype "passive"))
    )
    (net (code "14") (name "Net-(C28-Pad1)") (class "Default")
      (node (ref "C28") (pin "1") (pinfunction "1_1") (pintype "passive"))
      (node (ref "R29") (pin "2") (pinfunction "2_2") (pintype "passive"))
    )
    (net (code "15") (name "Net-(C32-Pad1)") (class "Default")
      (node (ref "C32") (pin "1") (pinfunction "1_1") (pintype "passive"))
      (node (ref "R34") (pin "2") (pinfunction "2_2") (pintype "passive"))
    )
    (net (code "16") (name "Net-(C36-Pad1)") (class "Default")
      (node (ref "C36") (pin "1") (pinfunction "1_1") (pintype "passive"))
      (node (ref "R39") (pin "2") (pinfunction "2_2") (pintype "passive"))
    )
    (net (code "17") (name "Net-(IC1-XTAL1)") (class "Default")
      (node (ref "C1") (pin "2") (pinfunction "2_2") (pintype "passive"))
      (node (ref "IC1") (pin "8") (pinfunction "XTAL1_8") (pintype "input"))
      (node (ref "Q1") (pin "1") (pinfunction "1_1") (pintype "passive"))
    )
    (net (code "18") (name "Net-(IC1-XTAL2)") (class "Default")
      (node (ref "C2") (pin "2") (pinfunction "2_2") (pintype "passive"))
      (node (ref "IC1") (pin "7") (pinfunction "XTAL2_7") (pintype "output"))
      (node (ref "Q1") (pin "2") (pinfunction "2_2") (pintype "passive"))
    )
    (net (code "19") (name "Net-(LED1-C)") (class "Default")
      (node (ref "C8") (pin "2") (pinfunction "2_2") (pintype "passive"))
      (node (ref "LED1") (pin "K") (pinfunction "C_K") (pintype "passive"))
      (node (ref "LED2") (pin "A") (pinfunction "A_A") (pintype "passive"))
      (node (ref "U$1") (pin "2") (pinfunction "OUT1_2") (pintype "bidirectional"))
      (node (ref "U$7") (pin "P$2") (pinfunction "2_P$2") (pintype "bidirectional"))
    )
    (net (code "20") (name "Net-(LED2-C)") (class "Default")
      (node (ref "LED1") (pin "A") (pinfunction "A_A") (pintype "passive"))
      (node (ref "LED2") (pin "K") (pinfunction "C_K") (pintype "passive"))
      (node (ref "R7") (pin "2") (pinfunction "2_2") (pintype "passive"))
    )
    (net (code "21") (name "Net-(LED3-C)") (class "Default")
      (node (ref "C12") (pin "2") (pinfunction "2_2") (pintype "passive"))
      (node (ref "LED3") (pin "K") (pinfunction "C_K") (pintype "passive"))
      (node (ref "LED4") (pin "A") (pinfunction "A_A") (pintype "passive"))
      (node (ref "U$10") (pin "P$2") (pinfunction "2_P$2") (pintype "bidirectional"))
      (node (ref "U$8") (pin "2") (pinfunction "OUT1_2") (pintype "bidirectional"))
    )
    (net (code "22") (name "Net-(LED4-C)") (class "Default")
      (node (ref "LED3") (pin "A") (pinfunction "A_A") (pintype "passive"))
      (node (ref "LED4") (pin "K") (pinfunction "C_K") (pintype "passive"))
      (node (ref "R12") (pin "2") (pinfunction "2_2") (pintype "passive"))
    )
    (net (code "23") (name "Net-(LED5-C)") (class "Default")
      (node (ref "C16") (pin "2") (pinfunction "2_2") (pintype "passive"))
      (node (ref "LED5") (pin "K") (pinfunction "C_K") (pintype "passive"))
      (node (ref "LED6") (pin "A") (pinfunction "A_A") (pintype "passive"))
      (node (ref "U$11") (pin "2") (pinfunction "OUT1_2") (pintype "bidirectional"))
      (node (ref "U$13") (pin "P$2") (pinfunction "2_P$2") (pintype "bidirectional"))
    )
    (net (code "24") (name "Net-(LED6-C)") (class "Default")
      (node (ref "LED5") (pin "A") (pinfunction "A_A") (pintype "passive"))
      (node (ref "LED6") (pin "K") (pinfunction "C_K") (pintype "passive"))
      (node (ref "R17") (pin "2") (pinfunction "2_2") (pintype "passive"))
    )
    (net (code "25") (name "Net-(LED7-C)") (class "Default")
      (node (ref "C20") (pin "2") (pinfunction "2_2") (pintype "passive"))
      (node (ref "LED7") (pin "K") (pinfunction "C_K") (pintype "passive"))
      (node (ref "LED8") (pin "A") (pinfunction "A_A") (pintype "passive"))
      (node (ref "U$14") (pin "2") (pinfunction "OUT1_2") (pintype "bidirectional"))
      (node (ref "U$16") (pin "P$2") (pinfunction "2_P$2") (pintype "bidirectional"))
    )
    (net (code "26") (name "Net-(LED8-C)") (class "Default")
      (node (ref "LED7") (pin "A") (pinfunction "A_A") (pintype "passive"))
      (node (ref "LED8") (pin "K") (pinfunction "C_K") (pintype "passive"))
      (node (ref "R22") (pin "2") (pinfunction "2_2") (pintype "passive"))
    )
    (net (code "27") (name "Net-(LED9-C)") (class "Default")
      (node (ref "C24") (pin "2") (pinfunction "2_2") (pintype "passive"))
      (node (ref "LED10") (pin "A") (pinfunction "A_A") (pintype "passive"))
      (node (ref "LED9") (pin "K") (pinfunction "C_K") (pintype "passive"))
      (node (ref "U$17") (pin "2") (pinfunction "OUT1_2") (pintype "bidirectional"))
      (node (ref "U$19") (pin "P$2") (pinfunction "2_P$2") (pintype "bidirectional"))
    )
    (net (code "28") (name "Net-(LED10-C)") (class "Default")
      (node (ref "LED10") (pin "K") (pinfunction "C_K") (pintype "passive"))
      (node (ref "LED9") (pin "A") (pinfunction "A_A") (pintype "passive"))
      (node (ref "R27") (pin "2") (pinfunction "2_2") (pintype "passive"))
    )
    (net (code "29") (name "Net-(LED11-C)") (class "Default")
      (node (ref "C28") (pin "2") (pinfunction "2_2") (pintype "passive"))
      (node (ref "LED11") (pin "K") (pinfunction "C_K") (pintype "passive"))
      (node (ref "LED12") (pin "A") (pinfunction "A_A") (pintype "passive"))
      (node (ref "U$20") (pin "2") (pinfunction "OUT1_2") (pintype "bidirectional"))
      (node (ref "U$22") (pin "P$2") (pinfunction "2_P$2") (pintype "bidirectional"))
    )
    (net (code "30") (name "Net-(LED12-C)") (class "Default")
      (node (ref "LED11") (pin "A") (pinfunction "A_A") (pintype "passive"))
      (node (ref "LED12") (pin "K") (pinfunction "C_K") (pintype "passive"))
      (node (ref "R32") (pin "2") (pinfunction "2_2") (pintype "passive"))
    )
    (net (code "31") (name "Net-(LED13-C)") (class "Default")
      (node (ref "C32") (pin "2") (pinfunction "2_2") (pintype "passive"))
      (node (ref "LED13") (pin "K") (pinfunction "C_K") (pintype "passive"))
      (node (ref "LED14") (pin "A") (pinfunction "A_A") (pintype "passive"))
      (node (ref "U$23") (pin "2") (pinfunction "OUT1_2") (pintype "bidirectional"))
      (node (ref "U$25") (pin "P$2") (pinfunction "2_P$2") (pintype "bidirectional"))
    )
    (net (code "32") (name "Net-(LED14-C)") (class "Default")
      (node (ref "LED13") (pin "A") (pinfunction "A_A") (pintype "passive"))
      (node (ref "LED14") (pin "K") (pinfunction "C_K") (pintype "passive"))
      (node (ref "R37") (pin "2") (pinfunction "2_2") (pintype "passive"))
    )
    (net (code "33") (name "Net-(LED15-C)") (class "Default")
      (node (ref "C36") (pin "2") (pinfunction "2_2") (pintype "passive"))
      (node (ref "LED15") (pin "K") (pinfunction "C_K") (pintype "passive"))
      (node (ref "LED16") (pin "A") (pinfunction "A_A") (pintype "passive"))
      (node (ref "U$26") (pin "2") (pinfunction "OUT1_2") (pintype "bidirectional"))
      (node (ref "U$28") (pin "P$2") (pinfunction "2_P$2") (pintype "bidirectional"))
    )
    (net (code "34") (name "Net-(LED16-C)") (class "Default")
      (node (ref "LED15") (pin "A") (pinfunction "A_A") (pintype "passive"))
      (node (ref "LED16") (pin "K") (pinfunction "C_K") (pintype "passive"))
      (node (ref "R42") (pin "2") (pinfunction "2_2") (pintype "passive"))
    )
    (net (code "35") (name "Net-(U$1-OUT2)") (class "Default")
      (node (ref "R4") (pin "1") (pinfunction "1_1") (pintype "passive"))
      (node (ref "R7") (pin "1") (pinfunction "1_1") (pintype "passive"))
      (node (ref "U$1") (pin "10") (pinfunction "OUT2_10") (pintype "bidirectional"))
      (node (ref "U$7") (pin "P$1") (pinfunction "1_P$1") (pintype "bidirectional"))
    )
    (net (code "36") (name "Net-(U$1-VREF)") (class "Default")
      (node (ref "R2") (pin "1") (pinfunction "1_1") (pintype "passive"))
      (node (ref "R3") (pin "1") (pinfunction "1_1") (pintype "passive"))
      (node (ref "U$1") (pin "4") (pinfunction "VREF_4") (pintype "bidirectional"))
    )
    (net (code "37") (name "Net-(U$1-VS)") (class "Default")
      (node (ref "C6") (pin "+") (pinfunction "+_+") (pintype "passive"))
      (node (ref "R3") (pin "2") (pinfunction "2_2") (pintype "passive"))
      (node (ref "U$1") (pin "8") (pinfunction "VS_8") (pintype "bidirectional"))
      (node (ref "U$30") (pin "1") (pinfunction "1_1") (pintype "passive"))
    )
    (net (code "38") (name "Net-(U$2-1_12V)") (class "Default")
      (node (ref "U$2") (pin "1") (pinfunction "1_12V_1") (pintype "bidirectional"))
      (node (ref "U$2") (pin "2") (pinfunction "2_12V_2") (pintype "bidirectional"))
      (node (ref "U$2") (pin "4") (pinfunction "4_12V_4") (pintype "bidirectional"))
      (node (ref "U$31") (pin "1") (pinfunction "1_1") (pintype "passive"))
    )
    (net (code "39") (name "Net-(U$2-6_5V)") (class "Default")
      (node (ref "C37") (pin "+") (pinfunction "+_+") (pintype "passive"))
      (node (ref "U$2") (pin "6") (pinfunction "6_5V_6") (pintype "bidirectional"))
      (node (ref "U$32") (pin "1") (pinfunction "1_1") (pintype "passive"))
    )
    (net (code "40") (name "Net-(U$8-VREF)") (class "Default")
      (node (ref "R43") (pin "1") (pinfunction "1_1") (pintype "passive"))
      (node (ref "R8") (pin "1") (pinfunction "1_1") (pintype "passive"))
      (node (ref "U$8") (pin "4") (pinfunction "VREF_4") (pintype "bidirectional"))
    )
    (net (code "41") (name "Net-(U$8-VS)") (class "Default")
      (node (ref "C10") (pin "+") (pinfunction "+_+") (pintype "passive"))
      (node (ref "R8") (pin "2") (pinfunction "2_2") (pintype "passive"))
      (node (ref "U$33") (pin "1") (pinfunction "1_1") (pintype "passive"))
      (node (ref "U$8") (pin "8") (pinfunction "VS_8") (pintype "bidirectional"))
    )
    (net (code "42") (name "Net-(U$10-1)") (class "Default")
      (node (ref "R12") (pin "1") (pinfunction "1_1") (pintype "passive"))
      (node (ref "R9") (pin "1") (pinfunction "1_1") (pintype "passive"))
      (node (ref "U$10") (pin "P$1") (pinfunction "1_P$1") (pintype "bidirectional"))
      (node (ref "U$8") (pin "10") (pinfunction "OUT2_10") (pintype "bidirectional"))
    )
    (net (code "43") (name "Net-(U$11-OUT2)") (class "Default")
      (node (ref "R14") (pin "1") (pinfunction "1_1") (pintype "passive"))
      (node (ref "R17") (pin "1") (pinfunction "1_1") (pintype "passive"))
      (node (ref "U$11") (pin "10") (pinfunction "OUT2_10") (pintype "bidirectional"))
      (node (ref "U$13") (pin "P$1") (pinfunction "1_P$1") (pintype "bidirectional"))
    )
    (net (code "44") (name "Net-(U$11-VREF)") (class "Default")
      (node (ref "R13") (pin "1") (pinfunction "1_1") (pintype "passive"))
      (node (ref "R44") (pin "1") (pinfunction "1_1") (pintype "passive"))
      (node (ref "U$11") (pin "4") (pinfunction "VREF_4") (pintype "bidirectional"))
    )
    (net (code "45") (name "Net-(U$11-VS)") (class "Default")
      (node (ref "C14") (pin "+") (pinfunction "+_+") (pintype "passive"))
      (node (ref "R13") (pin "2") (pinfunction "2_2") (pintype "passive"))
      (node (ref "U$11") (pin "8") (pinfunction "VS_8") (pintype "bidirectional"))
      (node (ref "U$34") (pin "1") (pinfunction "1_1") (pintype "passive"))
    )
    (net (code "46") (name "Net-(U$14-OUT2)") (class "Default")
      (node (ref "R19") (pin "1") (pinfunction "1_1") (pintype "passive"))
      (node (ref "R22") (pin "1") (pinfunction "1_1") (pintype "passive"))
      (node (ref "U$14") (pin "10") (pinfunction "OUT2_10") (pintype "bidirectional"))
      (node (ref "U$16") (pin "P$1") (pinfunction "1_P$1") (pintype "bidirectional"))
    )
    (net (code "47") (name "Net-(U$14-VREF)") (class "Default")
      (node (ref "R18") (pin "1") (pinfunction "1_1") (pintype "passive"))
      (node (ref "R45") (pin "1") (pinfunction "1_1") (pintype "passive"))
      (node (ref "U$14") (pin "4") (pinfunction "VREF_4") (pintype "bidirectional"))
    )
    (net (code "48") (name "Net-(U$14-VS)") (class "Default")
      (node (ref "C18") (pin "+") (pinfunction "+_+") (pintype "passive"))
      (node (ref "R18") (pin "2") (pinfunction "2_2") (pintype "passive"))
      (node (ref "U$14") (pin "8") (pinfunction "VS_8") (pintype "bidirectional"))
      (node (ref "U$35") (pin "1") (pinfunction "1_1") (pintype "passive"))
    )
    (net (code "49") (name "Net-(U$17-OUT2)") (class "Default")
      (node (ref "R24") (pin "1") (pinfunction "1_1") (pintype "passive"))
      (node (ref "R27") (pin "1") (pinfunction "1_1") (pintype "passive"))
      (node (ref "U$17") (pin "10") (pinfunction "OUT2_10") (pintype "bidirectional"))
      (node (ref "U$19") (pin "P$1") (pinfunction "1_P$1") (pintype "bidirectional"))
    )
    (net (code "50") (name "Net-(U$17-VREF)") (class "Default")
      (node (ref "R23") (pin "1") (pinfunction "1_1") (pintype "passive"))
      (node (ref "R46") (pin "1") (pinfunction "1_1") (pintype "passive"))
      (node (ref "U$17") (pin "4") (pinfunction "VREF_4") (pintype "bidirectional"))
    )
    (net (code "51") (name "Net-(U$17-VS)") (class "Default")
      (node (ref "C22") (pin "+") (pinfunction "+_+") (pintype "passive"))
      (node (ref "R23") (pin "2") (pinfunction "2_2") (pintype "passive"))
      (node (ref "U$17") (pin "8") (pinfunction "VS_8") (pintype "bidirectional"))
      (node (ref "U$36") (pin "1") (pinfunction "1_1") (pintype "passive"))
    )
    (net (code "52") (name "Net-(U$20-OUT2)") (class "Default")
      (node (ref "R29") (pin "1") (pinfunction "1_1") (pintype "passive"))
      (node (ref "R32") (pin "1") (pinfunction "1_1") (pintype "passive"))
      (node (ref "U$20") (pin "10") (pinfunction "OUT2_10") (pintype "bidirectional"))
      (node (ref "U$22") (pin "P$1") (pinfunction "1_P$1") (pintype "bidirectional"))
    )
    (net (code "53") (name "Net-(U$20-VREF)") (class "Default")
      (node (ref "R28") (pin "1") (pinfunction "1_1") (pintype "passive"))
      (node (ref "R47") (pin "1") (pinfunction "1_1") (pintype "passive"))
      (node (ref "U$20") (pin "4") (pinfunction "VREF_4") (pintype "bidirectional"))
    )
    (net (code "54") (name "Net-(U$20-VS)") (class "Default")
      (node (ref "C26") (pin "+") (pinfunction "+_+") (pintype "passive"))
      (node (ref "R28") (pin "2") (pinfunction "2_2") (pintype "passive"))
      (node (ref "U$20") (pin "8") (pinfunction "VS_8") (pintype "bidirectional"))
      (node (ref "U$37") (pin "1") (pinfunction "1_1") (pintype "passive"))
    )
    (net (code "55") (name "Net-(U$23-OUT2)") (class "Default")
      (node (ref "R34") (pin "1") (pinfunction "1_1") (pintype "passive"))
      (node (ref "R37") (pin "1") (pinfunction "1_1") (pintype "passive"))
      (node (ref "U$23") (pin "10") (pinfunction "OUT2_10") (pintype "bidirectional"))
      (node (ref "U$25") (pin "P$1") (pinfunction "1_P$1") (pintype "bidirectional"))
    )
    (net (code "56") (name "Net-(U$23-VREF)") (class "Default")
      (node (ref "R33") (pin "1") (pinfunction "1_1") (pintype "passive"))
      (node (ref "R48") (pin "1") (pinfunction "1_1") (pintype "passive"))
      (node (ref "U$23") (pin "4") (pinfunction "VREF_4") (pintype "bidirectional"))
    )
    (net (code "57") (name "Net-(U$23-VS)") (class "Default")
      (node (ref "C30") (pin "+") (pinfunction "+_+") (pintype "passive"))
      (node (ref "R33") (pin "2") (pinfunction "2_2") (pintype "passive"))
      (node (ref "U$23") (pin "8") (pinfunction "VS_8") (pintype "bidirectional"))
      (node (ref "U$38") (pin "1") (pinfunction "1_1") (pintype "passive"))
    )
    (net (code "58") (name "Net-(U$26-OUT2)") (class "Default")
      (node (ref "R39") (pin "1") (pinfunction "1_1") (pintype "passive"))
      (node (ref "R42") (pin "1") (pinfunction "1_1") (pintype "passive"))
      (node (ref "U$26") (pin "10") (pinfunction "OUT2_10") (pintype "bidirectional"))
      (node (ref "U$28") (pin "P$1") (pinfunction "1_P$1") (pintype "bidirectional"))
    )
    (net (code "59") (name "Net-(U$26-VREF)") (class "Default")
      (node (ref "R38") (pin "1") (pinfunction "1_1") (pintype "passive"))
      (node (ref "R49") (pin "1") (pinfunction "1_1") (pintype "passive"))
      (node (ref "U$26") (pin "4") (pinfunction "VREF_4") (pintype "bidirectional"))
    )
    (net (code "60") (name "Net-(U$26-VS)") (class "Default")
      (node (ref "C34") (pin "+") (pinfunction "+_+") (pintype "passive"))
      (node (ref "R38") (pin "2") (pinfunction "2_2") (pintype "passive"))
      (node (ref "U$26") (pin "8") (pinfunction "VS_8") (pintype "bidirectional"))
      (node (ref "U$39") (pin "1") (pinfunction "1_1") (pintype "passive"))
    )
    (net (code "61") (name "OUT_A_0") (class "Default")
      (node (ref "IC1") (pin "37") (pinfunction "(ADC0/PCINT0)PA0_37") (pintype "bidirectional"))
      (node (ref "R5") (pin "2") (pinfunction "2_2") (pintype "passive"))
      (node (ref "U$1") (pin "5") (pinfunction "IN1_5") (pintype "bidirectional"))
    )
    (net (code "62") (name "OUT_A_1") (class "Default")
      (node (ref "IC1") (pin "36") (pinfunction "(ADC1/PCINT1)PA1_36") (pintype "bidirectional"))
      (node (ref "R6") (pin "2") (pinfunction "2_2") (pintype "passive"))
      (node (ref "U$1") (pin "6") (pinfunction "IN2_6") (pintype "bidirectional"))
    )
    (net (code "63") (name "OUT_B_0") (class "Default")
      (node (ref "IC1") (pin "35") (pinfunction "(ADC2/PCINT2)PA2_35") (pintype "bidirectional"))
      (node (ref "R10") (pin "2") (pinfunction "2_2") (pintype "passive"))
      (node (ref "U$8") (pin "5") (pinfunction "IN1_5") (pintype "bidirectional"))
    )
    (net (code "64") (name "OUT_B_1") (class "Default")
      (node (ref "IC1") (pin "34") (pinfunction "(ADC3/PCINT3)PA3_34") (pintype "bidirectional"))
      (node (ref "R11") (pin "2") (pinfunction "2_2") (pintype "passive"))
      (node (ref "U$8") (pin "6") (pinfunction "IN2_6") (pintype "bidirectional"))
    )
    (net (code "65") (name "OUT_C_0") (class "Default")
      (node (ref "IC1") (pin "33") (pinfunction "(ADC4/PCINT4)PA4_33") (pintype "bidirectional"))
      (node (ref "R15") (pin "2") (pinfunction "2_2") (pintype "passive"))
      (node (ref "U$11") (pin "5") (pinfunction "IN1_5") (pintype "bidirectional"))
    )
    (net (code "66") (name "OUT_C_1") (class "Default")
      (node (ref "IC1") (pin "32") (pinfunction "(ADC5/PCINT5)PA5_32") (pintype "bidirectional"))
      (node (ref "R16") (pin "2") (pinfunction "2_2") (pintype "passive"))
      (node (ref "U$11") (pin "6") (pinfunction "IN2_6") (pintype "bidirectional"))
    )
    (net (code "67") (name "OUT_D_0") (class "Default")
      (node (ref "IC1") (pin "31") (pinfunction "(ADC6/PCINT6)PA6_31") (pintype "bidirectional"))
      (node (ref "R20") (pin "2") (pinfunction "2_2") (pintype "passive"))
      (node (ref "U$14") (pin "5") (pinfunction "IN1_5") (pintype "bidirectional"))
    )
    (net (code "68") (name "OUT_D_1") (class "Default")
      (node (ref "IC1") (pin "30") (pinfunction "(ADC7/PCINT7)PA7_30") (pintype "bidirectional"))
      (node (ref "R21") (pin "2") (pinfunction "2_2") (pintype "passive"))
      (node (ref "U$14") (pin "6") (pinfunction "IN2_6") (pintype "bidirectional"))
    )
    (net (code "69") (name "OUT_E_0") (class "Default")
      (node (ref "IC1") (pin "9") (pinfunction "(RXD0/PCINT24)PD0_9") (pintype "bidirectional"))
      (node (ref "R25") (pin "2") (pinfunction "2_2") (pintype "passive"))
      (node (ref "U$17") (pin "5") (pinfunction "IN1_5") (pintype "bidirectional"))
    )
    (net (code "70") (name "OUT_E_1") (class "Default")
      (node (ref "IC1") (pin "10") (pinfunction "(TXD0/PCINT25)PD1_10") (pintype "bidirectional"))
      (node (ref "R26") (pin "2") (pinfunction "2_2") (pintype "passive"))
      (node (ref "U$17") (pin "6") (pinfunction "IN2_6") (pintype "bidirectional"))
    )
    (net (code "71") (name "OUT_F_0") (class "Default")
      (node (ref "IC1") (pin "11") (pinfunction "(RXD1/INT0/PCINT26)PD2_11") (pintype "bidirectional"))
      (node (ref "R30") (pin "2") (pinfunction "2_2") (pintype "passive"))
      (node (ref "U$20") (pin "5") (pinfunction "IN1_5") (pintype "bidirectional"))
    )
    (net (code "72") (name "OUT_F_1") (class "Default")
      (node (ref "IC1") (pin "12") (pinfunction "(TXD1/INT1/PCINT27)PD3_12") (pintype "bidirectional"))
      (node (ref "R31") (pin "2") (pinfunction "2_2") (pintype "passive"))
      (node (ref "U$20") (pin "6") (pinfunction "IN2_6") (pintype "bidirectional"))
    )
    (net (code "73") (name "OUT_G_0") (class "Default")
      (node (ref "IC1") (pin "13") (pinfunction "(XCK1/OC1B/PCINT28)PD4_13") (pintype "bidirectional"))
      (node (ref "R35") (pin "2") (pinfunction "2_2") (pintype "passive"))
      (node (ref "U$23") (pin "5") (pinfunction "IN1_5") (pintype "bidirectional"))
    )
    (net (code "74") (name "OUT_G_1") (class "Default")
      (node (ref "IC1") (pin "14") (pinfunction "(OC1A/PCINT29)PD5_14") (pintype "bidirectional"))
      (node (ref "R36") (pin "2") (pinfunction "2_2") (pintype "passive"))
      (node (ref "U$23") (pin "6") (pinfunction "IN2_6") (pintype "bidirectional"))
    )
    (net (code "75") (name "OUT_H_0") (class "Default")
      (node (ref "IC1") (pin "15") (pinfunction "(OC2B/ICP/PCINT30)PD6_15") (pintype "bidirectional"))
      (node (ref "R40") (pin "2") (pinfunction "2_2") (pintype "passive"))
      (node (ref "U$26") (pin "5") (pinfunction "IN1_5") (pintype "bidirectional"))
    )
    (net (code "76") (name "OUT_H_1") (class "Default")
      (node (ref "IC1") (pin "16") (pinfunction "(OC2A/PCINT31)PD7_16") (pintype "bidirectional"))
      (node (ref "R41") (pin "2") (pinfunction "2_2") (pintype "passive"))
      (node (ref "U$26") (pin "6") (pinfunction "IN2_6") (pintype "bidirectional"))
    )
    (net (code "77") (name "SCK") (class "Default")
      (node (ref "IC1") (pin "3") (pinfunction "(SCK/PCINT15)PB7_3") (pintype "bidirectional"))
      (node (ref "U$2") (pin "13") (pinfunction "13_SCK_13") (pintype "bidirectional"))
    )
    (net (code "78") (name "TCK") (class "Default")
      (node (ref "IC1") (pin "21") (pinfunction "(TCK/PCINT18)PC2_21") (pintype "bidirectional"))
      (node (ref "JP1") (pin "1") (pinfunction "1_1") (pintype "passive"))
    )
    (net (code "79") (name "TDI") (class "Default")
      (node (ref "IC1") (pin "24") (pinfunction "(TDI/PCINT21)PC5_24") (pintype "bidirectional"))
      (node (ref "JP1") (pin "9") (pinfunction "9_9") (pintype "passive"))
    )
    (net (code "80") (name "TDO") (class "Default")
      (node (ref "IC1") (pin "23") (pinfunction "(TDO/PCINT20)PC4_23") (pintype "bidirectional"))
      (node (ref "JP1") (pin "3") (pinfunction "3_3") (pintype "passive"))
    )
    (net (code "81") (name "TMS") (class "Default")
      (node (ref "IC1") (pin "22") (pinfunction "(TMS/PCINT19)PC3_22") (pintype "bidirectional"))
      (node (ref "JP1") (pin "5") (pinfunction "5_5") (pintype "passive"))
    )
    (net (code "82") (name "unconnected-(IC1-(CLKO{slash}T1{slash}PCINT9)PB1-Pad41)") (class "Default")
      (node (ref "IC1") (pin "41") (pinfunction "(CLKO/T1/PCINT9)PB1_41") (pintype "bidirectional"))
    )
    (net (code "83") (name "unconnected-(IC1-(INT2{slash}AIN0{slash}PCINT10)PB2-Pad42)") (class "Default")
      (node (ref "IC1") (pin "42") (pinfunction "(INT2/AIN0/PCINT10)PB2_42") (pintype "bidirectional"))
    )
    (net (code "84") (name "unconnected-(IC1-(OC0A{slash}AIN1{slash}PCINT11)PB3-Pad43)") (class "Default")
      (node (ref "IC1") (pin "43") (pinfunction "(OC0A/AIN1/PCINT11)PB3_43") (pintype "bidirectional"))
    )
    (net (code "85") (name "unconnected-(IC1-(SCL{slash}PCINT16)PC0-Pad19)") (class "Default")
      (node (ref "IC1") (pin "19") (pinfunction "(SCL/PCINT16)PC0_19") (pintype "bidirectional"))
    )
    (net (code "86") (name "unconnected-(IC1-(SDA{slash}PCINT17)PC1-Pad20)") (class "Default")
      (node (ref "IC1") (pin "20") (pinfunction "(SDA/PCINT17)PC1_20") (pintype "bidirectional"))
    )
    (net (code "87") (name "unconnected-(IC1-(TOSC1{slash}PCINT22)PC6-Pad25)") (class "Default")
      (node (ref "IC1") (pin "25") (pinfunction "(TOSC1/PCINT22)PC6_25") (pintype "bidirectional"))
    )
    (net (code "88") (name "unconnected-(IC1-(TOSC2{slash}PCINT23)PC7-Pad26)") (class "Default")
      (node (ref "IC1") (pin "26") (pinfunction "(TOSC2/PCINT23)PC7_26") (pintype "bidirectional"))
    )
    (net (code "89") (name "unconnected-(IC1-(XCK0{slash}T0{slash}PCINT8)PB0-Pad40)") (class "Default")
      (node (ref "IC1") (pin "40") (pinfunction "(XCK0/T0/PCINT8)PB0_40") (pintype "bidirectional"))
    )
    (net (code "90") (name "unconnected-(JP1-Pad8)") (class "Default")
      (node (ref "JP1") (pin "8") (pinfunction "8_8") (pintype "passive"))
    )
    (net (code "91") (name "unconnected-(U$1-NC-Pad3)") (class "Default")
      (node (ref "U$1") (pin "3") (pinfunction "NC_3") (pintype "bidirectional"))
    )
    (net (code "92") (name "unconnected-(U$1-NC2-Pad9)") (class "Default")
      (node (ref "U$1") (pin "9") (pinfunction "NC2_9") (pintype "bidirectional"))
    )
    (net (code "93") (name "unconnected-(U$2-10_3.3V-Pad10)") (class "Default")
      (node (ref "U$2") (pin "10") (pinfunction "10_3.3V_10") (pintype "bidirectional"))
    )
    (net (code "94") (name "unconnected-(U$8-NC-Pad3)") (class "Default")
      (node (ref "U$8") (pin "3") (pinfunction "NC_3") (pintype "bidirectional"))
    )
    (net (code "95") (name "unconnected-(U$8-NC2-Pad9)") (class "Default")
      (node (ref "U$8") (pin "9") (pinfunction "NC2_9") (pintype "bidirectional"))
    )
    (net (code "96") (name "unconnected-(U$11-NC-Pad3)") (class "Default")
      (node (ref "U$11") (pin "3") (pinfunction "NC_3") (pintype "bidirectional"))
    )
    (net (code "97") (name "unconnected-(U$11-NC2-Pad9)") (class "Default")
      (node (ref "U$11") (pin "9") (pinfunction "NC2_9") (pintype "bidirectional"))
    )
    (net (code "98") (name "unconnected-(U$14-NC-Pad3)") (class "Default")
      (node (ref "U$14") (pin "3") (pinfunction "NC_3") (pintype "bidirectional"))
    )
    (net (code "99") (name "unconnected-(U$14-NC2-Pad9)") (class "Default")
      (node (ref "U$14") (pin "9") (pinfunction "NC2_9") (pintype "bidirectional"))
    )
    (net (code "100") (name "unconnected-(U$17-NC-Pad3)") (class "Default")
      (node (ref "U$17") (pin "3") (pinfunction "NC_3") (pintype "bidirectional"))
    )
    (net (code "101") (name "unconnected-(U$17-NC2-Pad9)") (class "Default")
      (node (ref "U$17") (pin "9") (pinfunction "NC2_9") (pintype "bidirectional"))
    )
    (net (code "102") (name "unconnected-(U$20-NC-Pad3)") (class "Default")
      (node (ref "U$20") (pin "3") (pinfunction "NC_3") (pintype "bidirectional"))
    )
    (net (code "103") (name "unconnected-(U$20-NC2-Pad9)") (class "Default")
      (node (ref "U$20") (pin "9") (pinfunction "NC2_9") (pintype "bidirectional"))
    )
    (net (code "104") (name "unconnected-(U$23-NC-Pad3)") (class "Default")
      (node (ref "U$23") (pin "3") (pinfunction "NC_3") (pintype "bidirectional"))
    )
    (net (code "105") (name "unconnected-(U$23-NC2-Pad9)") (class "Default")
      (node (ref "U$23") (pin "9") (pinfunction "NC2_9") (pintype "bidirectional"))
    )
    (net (code "106") (name "unconnected-(U$26-NC-Pad3)") (class "Default")
      (node (ref "U$26") (pin "3") (pinfunction "NC_3") (pintype "bidirectional"))
    )
    (net (code "107") (name "unconnected-(U$26-NC2-Pad9)") (class "Default")
      (node (ref "U$26") (pin "9") (pinfunction "NC2_9") (pintype "bidirectional"))
    )
  )
)
